# NOT_GATE.net
KiCad netlist of a schematic drawn in Altium Designer
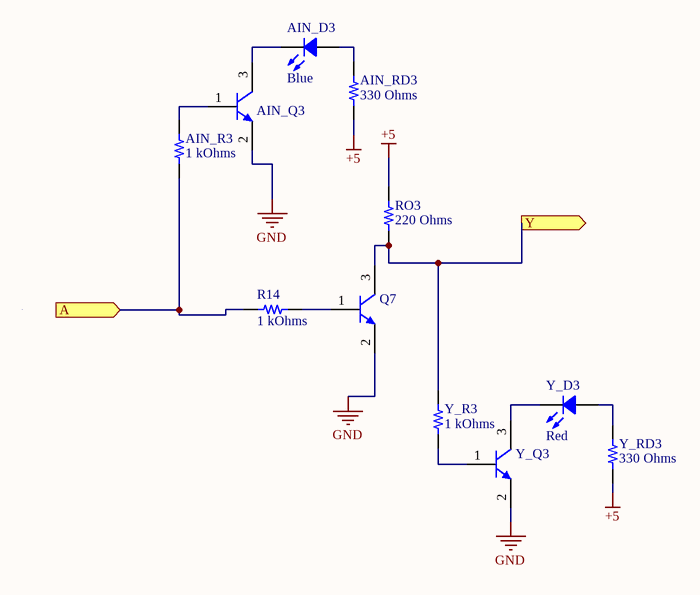
[diagram p0: NOT_GATE.SchDoc]

(export (version "E")
  (design (tool "Eeschema 10.0.6"))
  (components
    (comp (ref "AIN_D3")
      (value "Blue")
      (footprint "LED 0603_1608 BLUE")
      (description "LED BLUE CLEAR 0603 SMD")
      (fields (field (name "PART NUMBER") "IN-S63AT5B") (field (name "MANUFACTURER") "Inolux"))
      (libsource (lib "Celestial Altium Library - altium_library") (part "LED"))
    )
    (comp (ref "AIN_Q3")
      (value "MMSS8050-L-TP")
      (footprint "MCCSEMI SOT-23-3")
      (description "TRANS NPN 25V 1.5A SOT23")
      (fields (field (name "MANUFACTURER") "Micro Commercial Co"))
      (libsource (lib "Celestial Altium Library - altium_library") (part "MCCSEMI NPN SOT-23-3"))
    )
    (comp (ref "AIN_R3")
      (value "1 kOhms")
      (footprint "RES 0603_1608")
      (description "RES SMD 1K OHM 0.1% 1/16W 0603")
      (fields
        (field (name "PART NUMBER") "CPF0603B1K0E")
        (field (name "MANUFACTURER") "TE Connectivity Passive Product")
      )
      (libsource (lib "Celestial Altium Library - altium_library") (part "Resistor"))
    )
    (comp (ref "AIN_RD3")
      (value "330 Ohms")
      (footprint "RES 0603_1608")
      (description "RES 330 OHM 5% 1/10W 0603")
      (fields
        (field (name "PART NUMBER") "RMCF0603JT330R")
        (field (name "MANUFACTURER") "Stackpole Electronics Inc")
      )
      (libsource (lib "Celestial Altium Library - altium_library") (part "Resistor"))
    )
    (comp (ref "Q7")
      (value "MMSS8050-L-TP")
      (footprint "MCCSEMI SOT-23-3")
      (description "TRANS NPN 25V 1.5A SOT23")
      (fields (field (name "MANUFACTURER") "Micro Commercial Co"))
      (libsource (lib "Celestial Altium Library - altium_library") (part "MCCSEMI NPN SOT-23-3"))
    )
    (comp (ref "R14")
      (value "1 kOhms")
      (footprint "RES 0603_1608")
      (description "RES SMD 1K OHM 0.1% 1/16W 0603")
      (fields
        (field (name "PART NUMBER") "CPF0603B1K0E")
        (field (name "MANUFACTURER") "TE Connectivity Passive Product")
      )
      (libsource (lib "Celestial Altium Library - altium_library") (part "Resistor"))
    )
    (comp (ref "RO3")
      (value "220 Ohms")
      (footprint "RES 0603_1608")
      (description "RES SMD 220 OHM 0.5% 1/10W 0603")
      (fields
        (field (name "PART NUMBER") "ERA-3AED221V")
        (field (name "MANUFACTURER") "Panasonic Electronic Components")
      )
      (libsource (lib "Celestial Altium Library - altium_library") (part "Resistor"))
    )
    (comp (ref "Y_D3")
      (value "Red")
      (footprint "LED 0603_1608 RED")
      (description "LED RED CLEAR CHIP SMD")
      (fields (field (name "PART NUMBER") "XZMDK53W-8") (field (name "MANUFACTURER") "SunLED"))
      (libsource (lib "Celestial Altium Library - altium_library") (part "LED"))
    )
    (comp (ref "Y_Q3")
      (value "MMSS8050-L-TP")
      (footprint "MCCSEMI SOT-23-3")
      (description "TRANS NPN 25V 1.5A SOT23")
      (fields (field (name "MANUFACTURER") "Micro Commercial Co"))
      (libsource (lib "Celestial Altium Library - altium_library") (part "MCCSEMI NPN SOT-23-3"))
    )
    (comp (ref "Y_R3")
      (value "1 kOhms")
      (footprint "RES 0603_1608")
      (description "RES SMD 1K OHM 0.1% 1/16W 0603")
      (fields
        (field (name "PART NUMBER") "CPF0603B1K0E")
        (field (name "MANUFACTURER") "TE Connectivity Passive Product")
      )
      (libsource (lib "Celestial Altium Library - altium_library") (part "Resistor"))
    )
    (comp (ref "Y_RD3")
      (value "330 Ohms")
      (footprint "RES 0603_1608")
      (description "RES 330 OHM 5% 1/10W 0603")
      (fields
        (field (name "PART NUMBER") "RMCF0603JT330R")
        (field (name "MANUFACTURER") "Stackpole Electronics Inc")
      )
      (libsource (lib "Celestial Altium Library - altium_library") (part "Resistor"))
    )
  )
  (nets
    (net (code "1") (name "+5") (class "Default")
      (node (ref "AIN_RD3") (pin "1") (pinfunction "1_1") (pintype "passive"))
      (node (ref "RO3") (pin "2") (pinfunction "2_2") (pintype "passive"))
      (node (ref "Y_RD3") (pin "1") (pinfunction "1_1") (pintype "passive"))
    )
    (net (code "2") (name "/A") (class "Default")
      (node (ref "AIN_R3") (pin "2") (pinfunction "2_2") (pintype "passive"))
      (node (ref "R14") (pin "1") (pinfunction "1_1") (pintype "passive"))
    )
    (net (code "3") (name "/Y") (class "Default")
      (node (ref "Q7") (pin "3") (pinfunction "C_3") (pintype "passive"))
      (node (ref "RO3") (pin "1") (pinfunction "1_1") (pintype "passive"))
      (node (ref "Y_R3") (pin "2") (pinfunction "2_2") (pintype "passive"))
    )
    (net (code "4") (name "GND") (class "Default")
      (node (ref "AIN_Q3") (pin "2") (pinfunction "E_2") (pintype "passive"))
      (node (ref "Q7") (pin "2") (pinfunction "E_2") (pintype "passive"))
      (node (ref "Y_Q3") (pin "2") (pinfunction "E_2") (pintype "passive"))
    )
    (net (code "5") (name "Net-(AIN_D3-Pad1)") (class "Default")
      (node (ref "AIN_D3") (pin "1") (pinfunction "1_1") (pintype "passive"))
      (node (ref "AIN_RD3") (pin "2") (pinfunction "2_2") (pintype "passive"))
    )
    (net (code "6") (name "Net-(AIN_Q3-B)") (class "Default")
      (node (ref "AIN_Q3") (pin "1") (pinfunction "B_1") (pintype "passive"))
      (node (ref "AIN_R3") (pin "1") (pinfunction "1_1") (pintype "passive"))
    )
    (net (code "7") (name "Net-(AIN_Q3-C)") (class "Default")
      (node (ref "AIN_D3") (pin "2") (pinfunction "2_2") (pintype "passive"))
      (node (ref "AIN_Q3") (pin "3") (pinfunction "C_3") (pintype "passive"))
    )
    (net (code "8") (name "Net-(Q7-B)") (class "Default")
      (node (ref "Q7") (pin "1") (pinfunction "B_1") (pintype "passive"))
      (node (ref "R14") (pin "2") (pinfunction "2_2") (pintype "passive"))
    )
    (net (code "9") (name "Net-(Y_D3-Pad1)") (class "Default")
      (node (ref "Y_D3") (pin "1") (pinfunction "1_1") (pintype "passive"))
      (node (ref "Y_RD3") (pin "2") (pinfunction "2_2") (pintype "passive"))
    )
    (net (code "10") (name "Net-(Y_Q3-B)") (class "Default")
      (node (ref "Y_Q3") (pin "1") (pinfunction "B_1") (pintype "passive"))
      (node (ref "Y_R3") (pin "1") (pinfunction "1_1") (pintype "passive"))
    )
    (net (code "11") (name "Net-(Y_Q3-C)") (class "Default")
      (node (ref "Y_D3") (pin "2") (pinfunction "2_2") (pintype "passive"))
      (node (ref "Y_Q3") (pin "3") (pinfunction "C_3") (pintype "passive"))
    )
  )
)
